# timer-board.net
KiCad netlist of a schematic drawn in EAGLE
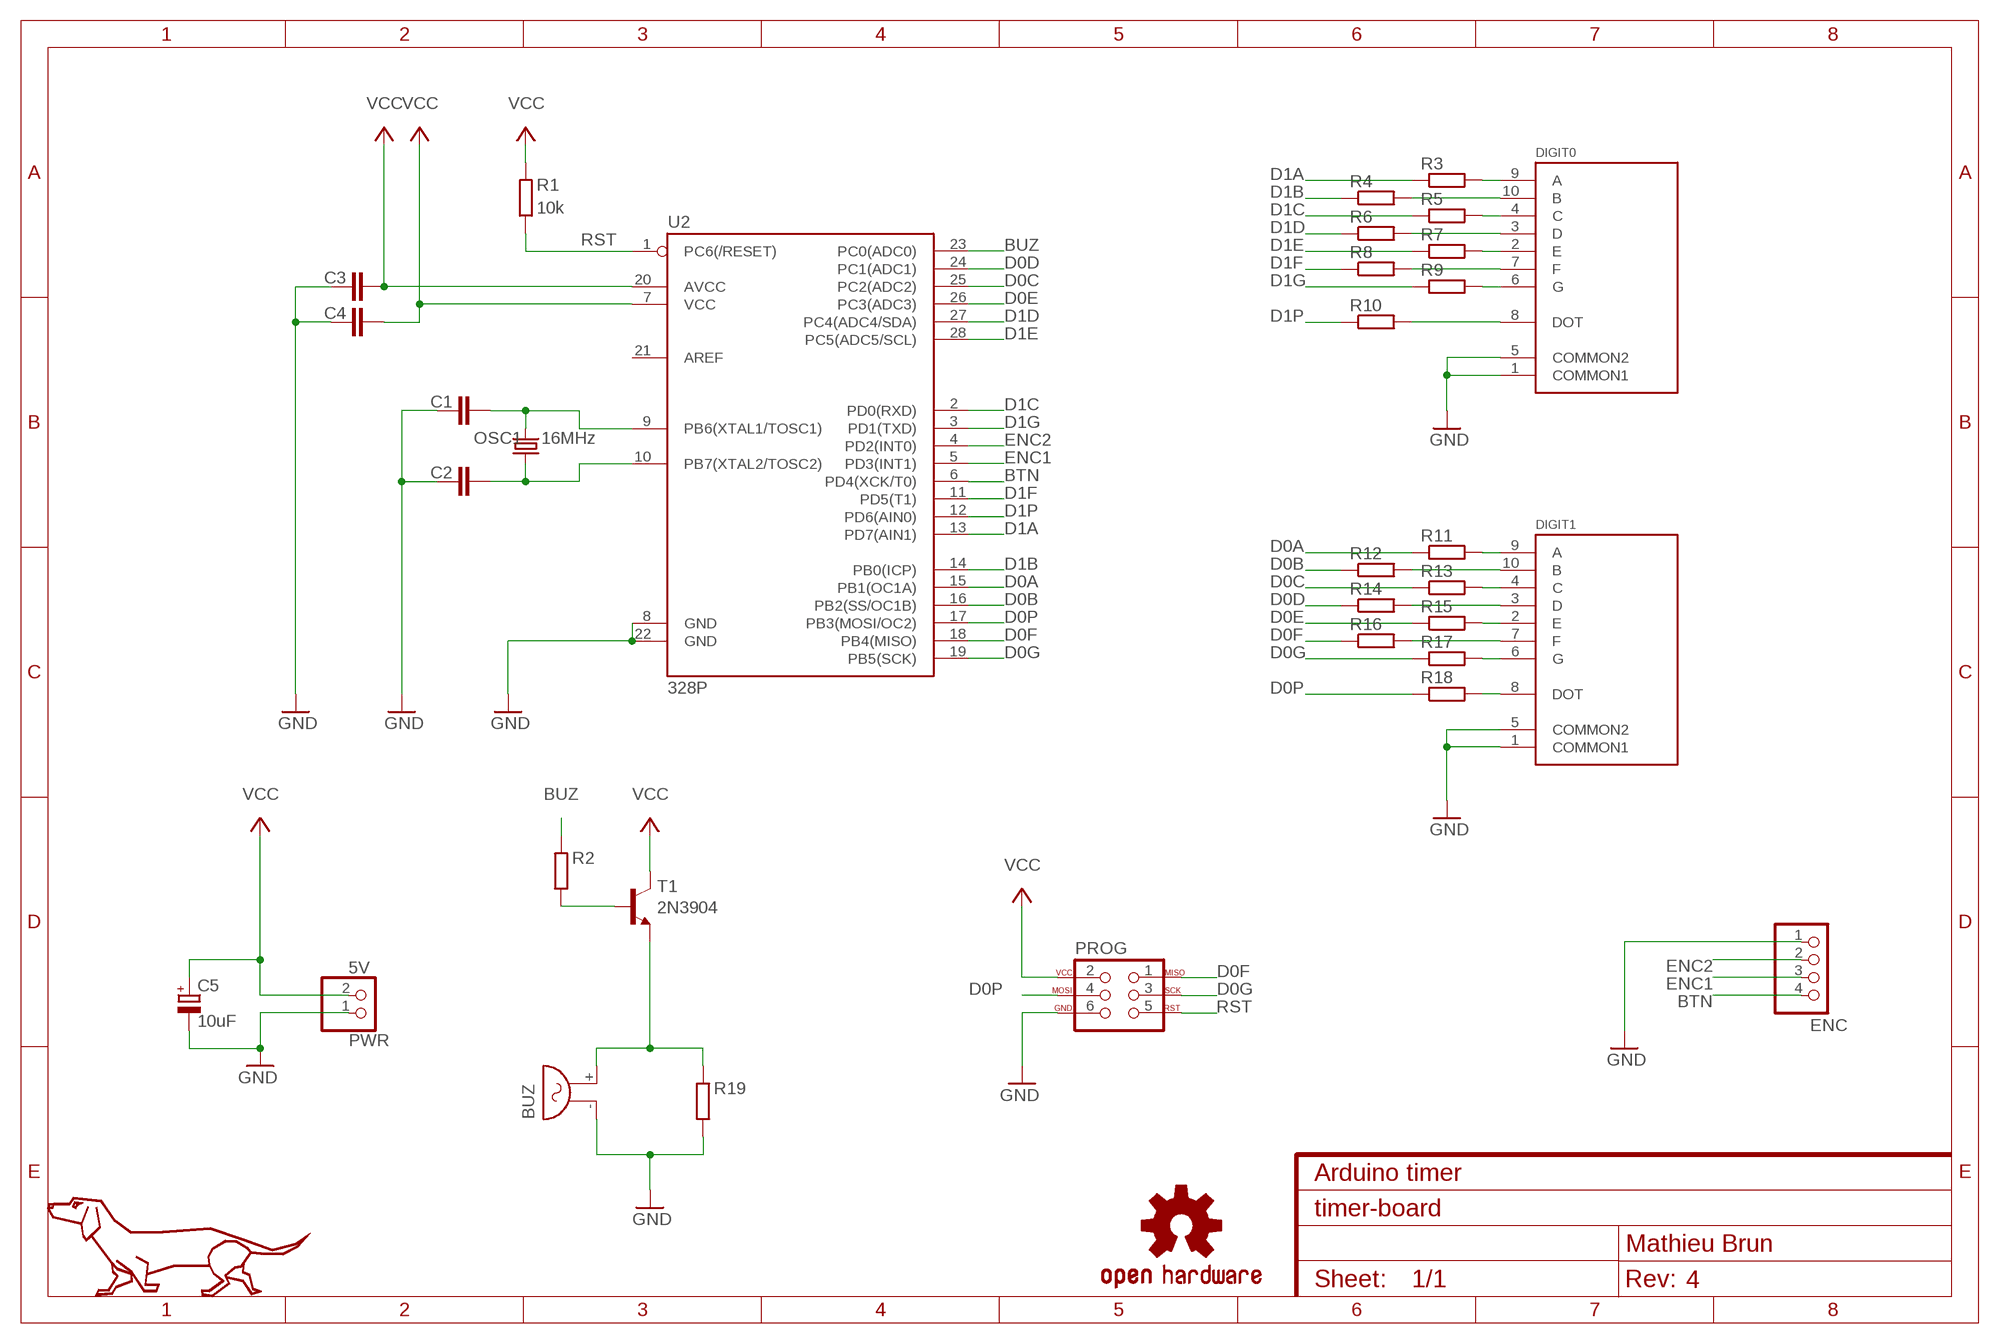
[diagram p0: schematic, sheet 1]

(export (version "E")
  (design (tool "Eeschema 10.0.6"))
  (components
    (comp (ref "BUZ")
      (value "BUZZER")
      (footprint "eagle-import:BUZZER")
      (libsource (lib "eagle-import") (part "BUZZER"))
    )
    (comp (ref "C1")
      (value "22pF")
      (footprint "eagle-import:C025-024X044")
      (libsource (lib "eagle-import") (part "C-EU025-024X044"))
    )
    (comp (ref "C2")
      (value "22pF")
      (footprint "eagle-import:C025-024X044")
      (libsource (lib "eagle-import") (part "C-EU025-024X044"))
    )
    (comp (ref "C3")
      (value "0.1uF")
      (footprint "eagle-import:C025-024X044")
      (libsource (lib "eagle-import") (part "C-EU025-024X044"))
    )
    (comp (ref "C4")
      (value "0.1uF")
      (footprint "eagle-import:C025-024X044")
      (libsource (lib "eagle-import") (part "C-EU025-024X044"))
    )
    (comp (ref "C5")
      (value "10uF")
      (footprint "eagle-import:E2,5-6")
      (libsource (lib "eagle-import") (part "CPOL-EUE2.5-6"))
    )
    (comp (ref "DIGIT0")
      (value "7_SEGMENT_DISPLAY")
      (footprint "eagle-import:7_SEGMENT_1.8_INCH")
      (libsource (lib "eagle-import") (part "7_SEGMENT_DISPLAY"))
    )
    (comp (ref "DIGIT1")
      (value "7_SEGMENT_DISPLAY")
      (footprint "eagle-import:7_SEGMENT_1.8_INCH")
      (libsource (lib "eagle-import") (part "7_SEGMENT_DISPLAY"))
    )
    (comp (ref "ENC")
      (value "CONN_1X5")
      (footprint "eagle-import:1X04_LOCK_JST")
      (libsource (lib "eagle-import") (part "CONN_1X4"))
    )
    (comp (ref "LOGO1")
      (value "OSHW-LOGOL")
      (footprint "eagle-import:OSHW-LOGO-L")
      (libsource (lib "eagle-import") (part "OSHW-LOGOL"))
    )
    (comp (ref "OSC1")
      (value "16MHz")
      (footprint "eagle-import:HC49US")
      (libsource (lib "eagle-import") (part "CRYSTAL-16MHZPTH-HC49US"))
    )
    (comp (ref "PROG")
      (value "AVR_SPI_PROG_3X22X3_LOCK")
      (footprint "eagle-import:2X3_LOCK")
      (libsource (lib "eagle-import") (part "AVR_SPI_PROG_3X22X3_LOCK"))
    )
    (comp (ref "PWR")
      (value "5V")
      (footprint "eagle-import:1X02_LOCK_JST")
      (libsource (lib "eagle-import") (part "CONN_1X2JST"))
    )
    (comp (ref "R1")
      (value "10k")
      (footprint "eagle-import:0207_10")
      (libsource (lib "eagle-import") (part "R-EU_0207/10"))
    )
    (comp (ref "R2")
      (value "R-EU_0207/10")
      (footprint "eagle-import:0207_10")
      (libsource (lib "eagle-import") (part "R-EU_0207/10"))
    )
    (comp (ref "R3")
      (value "R-EU_0207/10")
      (footprint "eagle-import:0207_10")
      (libsource (lib "eagle-import") (part "R-EU_0207/10"))
    )
    (comp (ref "R4")
      (value "R-EU_0207/10")
      (footprint "eagle-import:0207_10")
      (libsource (lib "eagle-import") (part "R-EU_0207/10"))
    )
    (comp (ref "R5")
      (value "R-EU_0207/10")
      (footprint "eagle-import:0207_10")
      (libsource (lib "eagle-import") (part "R-EU_0207/10"))
    )
    (comp (ref "R6")
      (value "R-EU_0207/10")
      (footprint "eagle-import:0207_10")
      (libsource (lib "eagle-import") (part "R-EU_0207/10"))
    )
    (comp (ref "R7")
      (value "R-EU_0207/10")
      (footprint "eagle-import:0207_10")
      (libsource (lib "eagle-import") (part "R-EU_0207/10"))
    )
    (comp (ref "R8")
      (value "R-EU_0207/10")
      (footprint "eagle-import:0207_10")
      (libsource (lib "eagle-import") (part "R-EU_0207/10"))
    )
    (comp (ref "R9")
      (value "R-EU_0207/10")
      (footprint "eagle-import:0207_10")
      (libsource (lib "eagle-import") (part "R-EU_0207/10"))
    )
    (comp (ref "R10")
      (value "R-EU_0207/10")
      (footprint "eagle-import:0207_10")
      (libsource (lib "eagle-import") (part "R-EU_0207/10"))
    )
    (comp (ref "R11")
      (value "R-EU_0207/10")
      (footprint "eagle-import:0207_10")
      (libsource (lib "eagle-import") (part "R-EU_0207/10"))
    )
    (comp (ref "R12")
      (value "R-EU_0207/10")
      (footprint "eagle-import:0207_10")
      (libsource (lib "eagle-import") (part "R-EU_0207/10"))
    )
    (comp (ref "R13")
      (value "R-EU_0207/10")
      (footprint "eagle-import:0207_10")
      (libsource (lib "eagle-import") (part "R-EU_0207/10"))
    )
    (comp (ref "R14")
      (value "R-EU_0207/10")
      (footprint "eagle-import:0207_10")
      (libsource (lib "eagle-import") (part "R-EU_0207/10"))
    )
    (comp (ref "R15")
      (value "R-EU_0207/10")
      (footprint "eagle-import:0207_10")
      (libsource (lib "eagle-import") (part "R-EU_0207/10"))
    )
    (comp (ref "R16")
      (value "R-EU_0207/10")
      (footprint "eagle-import:0207_10")
      (libsource (lib "eagle-import") (part "R-EU_0207/10"))
    )
    (comp (ref "R17")
      (value "R-EU_0207/10")
      (footprint "eagle-import:0207_10")
      (libsource (lib "eagle-import") (part "R-EU_0207/10"))
    )
    (comp (ref "R18")
      (value "R-EU_0207/10")
      (footprint "eagle-import:0207_10")
      (libsource (lib "eagle-import") (part "R-EU_0207/10"))
    )
    (comp (ref "R19")
      (value "R-EU_0207/10")
      (footprint "eagle-import:0207_10")
      (libsource (lib "eagle-import") (part "R-EU_0207/10"))
    )
    (comp (ref "T1")
      (value "2N3904")
      (footprint "eagle-import:TO92")
      (libsource (lib "eagle-import") (part "2N3904"))
    )
    (comp (ref "U$1")
      (value "LOGO_DOG")
      (footprint "eagle-import:LOGO_DOG")
      (libsource (lib "eagle-import") (part "LOGO_DOG"))
    )
    (comp (ref "U2")
      (value "328P")
      (footprint "eagle-import:DIP28")
      (libsource (lib "eagle-import") (part "ATMEGA328P_PDIP"))
    )
  )
  (nets
    (net (code "1") (name "/BTN") (class "Default")
      (node (ref "ENC") (pin "4") (pinfunction "4_4") (pintype "passive"))
      (node (ref "U2") (pin "6") (pinfunction "PD4(XCK/T0)_6") (pintype "bidirectional"))
    )
    (net (code "2") (name "/BUZ") (class "Default")
      (node (ref "R2") (pin "2") (pinfunction "2_2") (pintype "passive"))
      (node (ref "U2") (pin "23") (pinfunction "PC0(ADC0)_23") (pintype "bidirectional"))
    )
    (net (code "3") (name "/D0A") (class "Default")
      (node (ref "R11") (pin "1") (pinfunction "1_1") (pintype "passive"))
      (node (ref "U2") (pin "15") (pinfunction "PB1(OC1A)_15") (pintype "bidirectional"))
    )
    (net (code "4") (name "/D0B") (class "Default")
      (node (ref "R12") (pin "1") (pinfunction "1_1") (pintype "passive"))
      (node (ref "U2") (pin "16") (pinfunction "PB2(SS/OC1B)_16") (pintype "bidirectional"))
    )
    (net (code "5") (name "/D0C") (class "Default")
      (node (ref "R13") (pin "1") (pinfunction "1_1") (pintype "passive"))
      (node (ref "U2") (pin "25") (pinfunction "PC2(ADC2)_25") (pintype "bidirectional"))
    )
    (net (code "6") (name "/D0D") (class "Default")
      (node (ref "R14") (pin "1") (pinfunction "1_1") (pintype "passive"))
      (node (ref "U2") (pin "24") (pinfunction "PC1(ADC1)_24") (pintype "bidirectional"))
    )
    (net (code "7") (name "/D0E") (class "Default")
      (node (ref "R15") (pin "1") (pinfunction "1_1") (pintype "passive"))
      (node (ref "U2") (pin "26") (pinfunction "PC3(ADC3)_26") (pintype "bidirectional"))
    )
    (net (code "8") (name "/D0F") (class "Default")
      (node (ref "PROG") (pin "1") (pinfunction "1_1") (pintype "passive"))
      (node (ref "R16") (pin "1") (pinfunction "1_1") (pintype "passive"))
      (node (ref "U2") (pin "18") (pinfunction "PB4(MISO)_18") (pintype "bidirectional"))
    )
    (net (code "9") (name "/D0G") (class "Default")
      (node (ref "PROG") (pin "3") (pinfunction "3_3") (pintype "passive"))
      (node (ref "R17") (pin "1") (pinfunction "1_1") (pintype "passive"))
      (node (ref "U2") (pin "19") (pinfunction "PB5(SCK)_19") (pintype "bidirectional"))
    )
    (net (code "10") (name "/D0P") (class "Default")
      (node (ref "PROG") (pin "4") (pinfunction "4_4") (pintype "passive"))
      (node (ref "R18") (pin "1") (pinfunction "1_1") (pintype "passive"))
      (node (ref "U2") (pin "17") (pinfunction "PB3(MOSI/OC2)_17") (pintype "bidirectional"))
    )
    (net (code "11") (name "/D1A") (class "Default")
      (node (ref "R3") (pin "1") (pinfunction "1_1") (pintype "passive"))
      (node (ref "U2") (pin "13") (pinfunction "PD7(AIN1)_13") (pintype "bidirectional"))
    )
    (net (code "12") (name "/D1B") (class "Default")
      (node (ref "R4") (pin "1") (pinfunction "1_1") (pintype "passive"))
      (node (ref "U2") (pin "14") (pinfunction "PB0(ICP)_14") (pintype "bidirectional"))
    )
    (net (code "13") (name "/D1C") (class "Default")
      (node (ref "R5") (pin "1") (pinfunction "1_1") (pintype "passive"))
      (node (ref "U2") (pin "2") (pinfunction "PD0(RXD)_2") (pintype "bidirectional"))
    )
    (net (code "14") (name "/D1D") (class "Default")
      (node (ref "R6") (pin "1") (pinfunction "1_1") (pintype "passive"))
      (node (ref "U2") (pin "27") (pinfunction "PC4(ADC4/SDA)_27") (pintype "bidirectional"))
    )
    (net (code "15") (name "/D1E") (class "Default")
      (node (ref "R7") (pin "1") (pinfunction "1_1") (pintype "passive"))
      (node (ref "U2") (pin "28") (pinfunction "PC5(ADC5/SCL)_28") (pintype "bidirectional"))
    )
    (net (code "16") (name "/D1F") (class "Default")
      (node (ref "R8") (pin "1") (pinfunction "1_1") (pintype "passive"))
      (node (ref "U2") (pin "11") (pinfunction "PD5(T1)_11") (pintype "bidirectional"))
    )
    (net (code "17") (name "/D1G") (class "Default")
      (node (ref "R9") (pin "1") (pinfunction "1_1") (pintype "passive"))
      (node (ref "U2") (pin "3") (pinfunction "PD1(TXD)_3") (pintype "bidirectional"))
    )
    (net (code "18") (name "/D1P") (class "Default")
      (node (ref "R10") (pin "1") (pinfunction "1_1") (pintype "passive"))
      (node (ref "U2") (pin "12") (pinfunction "PD6(AIN0)_12") (pintype "bidirectional"))
    )
    (net (code "19") (name "/ENC1") (class "Default")
      (node (ref "ENC") (pin "3") (pinfunction "3_3") (pintype "passive"))
      (node (ref "U2") (pin "5") (pinfunction "PD3(INT1)_5") (pintype "bidirectional"))
    )
    (net (code "20") (name "/ENC2") (class "Default")
      (node (ref "ENC") (pin "2") (pinfunction "2_2") (pintype "passive"))
      (node (ref "U2") (pin "4") (pinfunction "PD2(INT0)_4") (pintype "bidirectional"))
    )
    (net (code "21") (name "/RST") (class "Default")
      (node (ref "PROG") (pin "5") (pinfunction "5_5") (pintype "passive"))
      (node (ref "R1") (pin "1") (pinfunction "1_1") (pintype "passive"))
      (node (ref "U2") (pin "1") (pinfunction "PC6(/RESET)_1") (pintype "bidirectional"))
    )
    (net (code "22") (name "GND") (class "Default")
      (node (ref "BUZ") (pin "-") (pinfunction "1_-") (pintype "passive"))
      (node (ref "C1") (pin "1") (pinfunction "1_1") (pintype "passive"))
      (node (ref "C2") (pin "1") (pinfunction "1_1") (pintype "passive"))
      (node (ref "C3") (pin "2") (pinfunction "2_2") (pintype "passive"))
      (node (ref "C4") (pin "2") (pinfunction "2_2") (pintype "passive"))
      (node (ref "C5") (pin "-") (pinfunction "-_-") (pintype "passive"))
      (node (ref "DIGIT0") (pin "1") (pinfunction "COMMON1_1") (pintype "bidirectional"))
      (node (ref "DIGIT0") (pin "5") (pinfunction "COMMON2_5") (pintype "bidirectional"))
      (node (ref "DIGIT1") (pin "1") (pinfunction "COMMON1_1") (pintype "bidirectional"))
      (node (ref "DIGIT1") (pin "5") (pinfunction "COMMON2_5") (pintype "bidirectional"))
      (node (ref "ENC") (pin "1") (pinfunction "1_1") (pintype "passive"))
      (node (ref "PROG") (pin "6") (pinfunction "6_6") (pintype "passive"))
      (node (ref "PWR") (pin "1") (pinfunction "1_1") (pintype "passive"))
      (node (ref "R19") (pin "1") (pinfunction "1_1") (pintype "passive"))
      (node (ref "U2") (pin "22") (pinfunction "GND_22") (pintype "bidirectional"))
      (node (ref "U2") (pin "8") (pinfunction "GND_8") (pintype "bidirectional"))
    )
    (net (code "23") (name "Net-(BUZ-2)") (class "Default")
      (node (ref "BUZ") (pin "+") (pinfunction "2_+") (pintype "passive"))
      (node (ref "R19") (pin "2") (pinfunction "2_2") (pintype "passive"))
      (node (ref "T1") (pin "3") (pinfunction "E_3") (pintype "passive"))
    )
    (net (code "24") (name "Net-(DIGIT0-A)") (class "Default")
      (node (ref "DIGIT0") (pin "9") (pinfunction "A_9") (pintype "bidirectional"))
      (node (ref "R3") (pin "2") (pinfunction "2_2") (pintype "passive"))
    )
    (net (code "25") (name "Net-(DIGIT0-B)") (class "Default")
      (node (ref "DIGIT0") (pin "10") (pinfunction "B_10") (pintype "bidirectional"))
      (node (ref "R4") (pin "2") (pinfunction "2_2") (pintype "passive"))
    )
    (net (code "26") (name "Net-(DIGIT0-C)") (class "Default")
      (node (ref "DIGIT0") (pin "4") (pinfunction "C_4") (pintype "bidirectional"))
      (node (ref "R5") (pin "2") (pinfunction "2_2") (pintype "passive"))
    )
    (net (code "27") (name "Net-(DIGIT0-D)") (class "Default")
      (node (ref "DIGIT0") (pin "3") (pinfunction "D_3") (pintype "bidirectional"))
      (node (ref "R6") (pin "2") (pinfunction "2_2") (pintype "passive"))
    )
    (net (code "28") (name "Net-(DIGIT0-DOT)") (class "Default")
      (node (ref "DIGIT0") (pin "8") (pinfunction "DOT_8") (pintype "bidirectional"))
      (node (ref "R10") (pin "2") (pinfunction "2_2") (pintype "passive"))
    )
    (net (code "29") (name "Net-(DIGIT0-E)") (class "Default")
      (node (ref "DIGIT0") (pin "2") (pinfunction "E_2") (pintype "bidirectional"))
      (node (ref "R7") (pin "2") (pinfunction "2_2") (pintype "passive"))
    )
    (net (code "30") (name "Net-(DIGIT0-F)") (class "Default")
      (node (ref "DIGIT0") (pin "7") (pinfunction "F_7") (pintype "bidirectional"))
      (node (ref "R8") (pin "2") (pinfunction "2_2") (pintype "passive"))
    )
    (net (code "31") (name "Net-(DIGIT0-G)") (class "Default")
      (node (ref "DIGIT0") (pin "6") (pinfunction "G_6") (pintype "bidirectional"))
      (node (ref "R9") (pin "2") (pinfunction "2_2") (pintype "passive"))
    )
    (net (code "32") (name "Net-(DIGIT1-A)") (class "Default")
      (node (ref "DIGIT1") (pin "9") (pinfunction "A_9") (pintype "bidirectional"))
      (node (ref "R11") (pin "2") (pinfunction "2_2") (pintype "passive"))
    )
    (net (code "33") (name "Net-(DIGIT1-B)") (class "Default")
      (node (ref "DIGIT1") (pin "10") (pinfunction "B_10") (pintype "bidirectional"))
      (node (ref "R12") (pin "2") (pinfunction "2_2") (pintype "passive"))
    )
    (net (code "34") (name "Net-(DIGIT1-C)") (class "Default")
      (node (ref "DIGIT1") (pin "4") (pinfunction "C_4") (pintype "bidirectional"))
      (node (ref "R13") (pin "2") (pinfunction "2_2") (pintype "passive"))
    )
    (net (code "35") (name "Net-(DIGIT1-D)") (class "Default")
      (node (ref "DIGIT1") (pin "3") (pinfunction "D_3") (pintype "bidirectional"))
      (node (ref "R14") (pin "2") (pinfunction "2_2") (pintype "passive"))
    )
    (net (code "36") (name "Net-(DIGIT1-DOT)") (class "Default")
      (node (ref "DIGIT1") (pin "8") (pinfunction "DOT_8") (pintype "bidirectional"))
      (node (ref "R18") (pin "2") (pinfunction "2_2") (pintype "passive"))
    )
    (net (code "37") (name "Net-(DIGIT1-E)") (class "Default")
      (node (ref "DIGIT1") (pin "2") (pinfunction "E_2") (pintype "bidirectional"))
      (node (ref "R15") (pin "2") (pinfunction "2_2") (pintype "passive"))
    )
    (net (code "38") (name "Net-(DIGIT1-F)") (class "Default")
      (node (ref "DIGIT1") (pin "7") (pinfunction "F_7") (pintype "bidirectional"))
      (node (ref "R16") (pin "2") (pinfunction "2_2") (pintype "passive"))
    )
    (net (code "39") (name "Net-(DIGIT1-G)") (class "Default")
      (node (ref "DIGIT1") (pin "6") (pinfunction "G_6") (pintype "bidirectional"))
      (node (ref "R17") (pin "2") (pinfunction "2_2") (pintype "passive"))
    )
    (net (code "40") (name "Net-(T1-B)") (class "Default")
      (node (ref "R2") (pin "1") (pinfunction "1_1") (pintype "passive"))
      (node (ref "T1") (pin "2") (pinfunction "B_2") (pintype "passive"))
    )
    (net (code "41") (name "Net-(U2-PB6(XTAL1{slash}TOSC1))") (class "Default")
      (node (ref "C1") (pin "2") (pinfunction "2_2") (pintype "passive"))
      (node (ref "OSC1") (pin "2") (pinfunction "2_2") (pintype "passive"))
      (node (ref "U2") (pin "9") (pinfunction "PB6(XTAL1/TOSC1)_9") (pintype "bidirectional"))
    )
    (net (code "42") (name "Net-(U2-PB7(XTAL2{slash}TOSC2))") (class "Default")
      (node (ref "C2") (pin "2") (pinfunction "2_2") (pintype "passive"))
      (node (ref "OSC1") (pin "1") (pinfunction "1_1") (pintype "passive"))
      (node (ref "U2") (pin "10") (pinfunction "PB7(XTAL2/TOSC2)_10") (pintype "bidirectional"))
    )
    (net (code "43") (name "VCC") (class "Default")
      (node (ref "C3") (pin "1") (pinfunction "1_1") (pintype "passive"))
      (node (ref "C4") (pin "1") (pinfunction "1_1") (pintype "passive"))
      (node (ref "C5") (pin "+") (pinfunction "+_+") (pintype "passive"))
      (node (ref "PROG") (pin "2") (pinfunction "2_2") (pintype "passive"))
      (node (ref "PWR") (pin "2") (pinfunction "2_2") (pintype "passive"))
      (node (ref "R1") (pin "2") (pinfunction "2_2") (pintype "passive"))
      (node (ref "T1") (pin "1") (pinfunction "C_1") (pintype "passive"))
      (node (ref "U2") (pin "20") (pinfunction "AVCC_20") (pintype "bidirectional"))
      (node (ref "U2") (pin "7") (pinfunction "VCC_7") (pintype "bidirectional"))
    )
    (net (code "44") (name "unconnected-(U2-AREF-Pad21)") (class "Default")
      (node (ref "U2") (pin "21") (pinfunction "AREF_21") (pintype "bidirectional"))
    )
  )
)
